# Sheet_1.net
KiCad netlist of a schematic drawn in Altium Designer
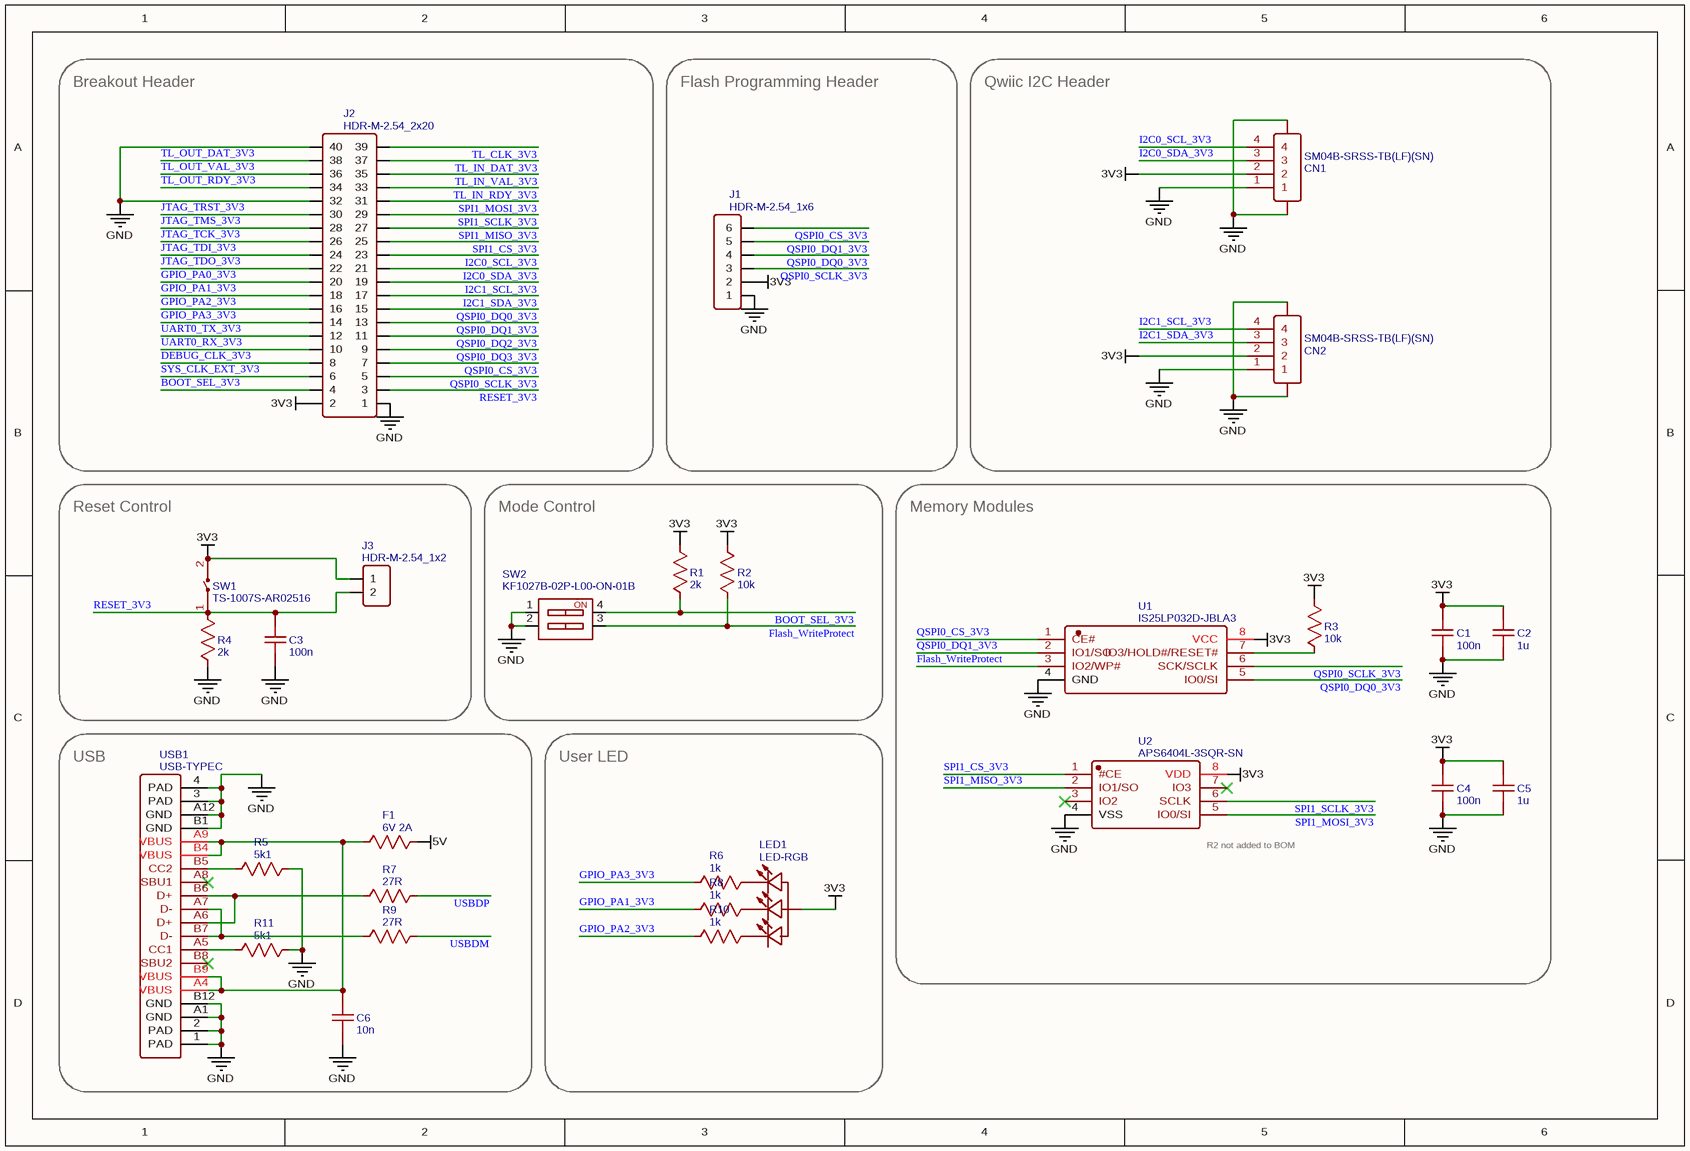
[diagram p0: Sheet_1.schdoc]

(export (version "E")
  (design (tool "Eeschema 10.0.6"))
  (components
    (comp (ref "C1")
      (value "100n")
      (footprint "CAPA-0402")
      (fields
        (field (name "BOM_SUPPLIER PART") "C307331")
        (field (name "BOM_MANUFACTURER PART") "CL05B104KB54PNC")
      )
      (libsource (lib "altium-import") (part "root_1_100n_"))
    )
    (comp (ref "C2")
      (value "1u")
      (footprint "CAPA-0402")
      (fields
        (field (name "BOM_SUPPLIER PART") "C52923")
        (field (name "BOM_MANUFACTURER PART") "CL05A105KA5NQNC")
      )
      (libsource (lib "altium-import") (part "root_1_1u_"))
    )
    (comp (ref "C3")
      (value "100n")
      (footprint "CAPA-0402")
      (fields
        (field (name "BOM_SUPPLIER PART") "C307331")
        (field (name "BOM_MANUFACTURER PART") "CL05B104KB54PNC")
      )
      (libsource (lib "altium-import") (part "root_1_100n_"))
    )
    (comp (ref "C4")
      (value "100n")
      (footprint "CAPA-0402")
      (fields
        (field (name "BOM_SUPPLIER PART") "C307331")
        (field (name "BOM_MANUFACTURER PART") "CL05B104KB54PNC")
      )
      (libsource (lib "altium-import") (part "root_1_100n_"))
    )
    (comp (ref "C5")
      (value "1u")
      (footprint "CAPA-0402")
      (fields
        (field (name "BOM_SUPPLIER PART") "C52923")
        (field (name "BOM_MANUFACTURER PART") "CL05A105KA5NQNC")
      )
      (libsource (lib "altium-import") (part "root_1_1u_"))
    )
    (comp (ref "C6")
      (value "10n")
      (footprint "CAPA-0402")
      (fields
        (field (name "BOM_SUPPLIER PART") "C15195")
        (field (name "BOM_MANUFACTURER PART") "CL05B103KB5NNNC")
      )
      (libsource (lib "altium-import") (part "root_1_10n_"))
    )
    (comp (ref "CN1")
      (value "SM04B-SRSS-TB(LF)(SN)")
      (footprint "CONN-SMD_4P-P1.00_SM04B-SRSS-TB-LF-SN")
      (fields (field (name "BOM_SUPPLIER PART") "C160404"))
      (libsource (lib "altium-import") (part "root_0_SM04B-SRSS-TB(LF)(SN)_"))
    )
    (comp (ref "CN2")
      (value "SM04B-SRSS-TB(LF)(SN)")
      (footprint "CONN-SMD_4P-P1.00_SM04B-SRSS-TB-LF-SN")
      (fields (field (name "BOM_SUPPLIER PART") "C160404"))
      (libsource (lib "altium-import") (part "root_0_SM04B-SRSS-TB(LF)(SN)_"))
    )
    (comp (ref "F1")
      (value "6V 2A")
      (footprint "R0805")
      (fields
        (field (name "BOM_SUPPLIER PART") "C70158")
        (field (name "BOM_MANUFACTURER PART") "SL0805200")
        (field (name "CONTRIBUTOR") "LCEDA_Lib")
      )
      (libsource (lib "altium-import") (part "root_0_6V 2A_"))
    )
    (comp (ref "J1")
      (value "HDR-M-2.54_1x6")
      (footprint "HDR-M-2.54_1X6")
      (fields (field (name "BOM_SUPPLIER PART") "C190819") (field (name "CONTRIBUTOR") "LCEDA_Lib"))
      (libsource (lib "altium-import") (part "root_2_HDR-M-2.54_1x6_"))
    )
    (comp (ref "J2")
      (value "HDR-M-2.54_2x20")
      (footprint "HDR-M-2.54_2X20")
      (fields (field (name "BOM_SUPPLIER PART") "C50980") (field (name "CONTRIBUTOR") "LCEDA_Lib"))
      (libsource (lib "altium-import") (part "root_2_HDR-M-2.54_2x20_"))
    )
    (comp (ref "J3")
      (value "HDR-M-2.54_1x2")
      (footprint "HDR-M-2.54_1X2")
      (fields (field (name "BOM_SUPPLIER PART") "C124375") (field (name "CONTRIBUTOR") "LCEDA_Lib"))
      (libsource (lib "altium-import") (part "root_0_HDR-M-2.54_1x2_"))
    )
    (comp (ref "LED1")
      (value "LED-RGB")
      (footprint "LED-ARRAY-SMD_4P-L3.2-W2.7-TL-RD_TJ-S3528")
      (fields
        (field (name "BOM_SUPPLIER PART") "C601699")
        (field (name "BOM_MANUFACTURER PART") "TJ-S3528UG2W9TLCCYRGB-A5")
      )
      (libsource (lib "altium-import") (part "root_0_LED-RGB_"))
    )
    (comp (ref "R1")
      (value "2k")
      (footprint "RES-0402")
      (fields
        (field (name "BOM_SUPPLIER PART") "C4109")
        (field (name "BOM_MANUFACTURER PART") "0402WGF2001TCE")
      )
      (libsource (lib "altium-import") (part "root_1_2k_"))
    )
    (comp (ref "R2")
      (value "10k")
      (footprint "RES-0402")
      (fields
        (field (name "BOM_SUPPLIER PART") "C25744")
        (field (name "BOM_MANUFACTURER PART") "0402WGF1002TCE")
      )
      (libsource (lib "altium-import") (part "root_1_10k_"))
    )
    (comp (ref "R3")
      (value "10k")
      (footprint "RES-0402")
      (fields
        (field (name "BOM_SUPPLIER PART") "C25744")
        (field (name "BOM_MANUFACTURER PART") "0402WGF1002TCE")
      )
      (libsource (lib "altium-import") (part "root_1_10k_"))
    )
    (comp (ref "R4")
      (value "2k")
      (footprint "RES-0402")
      (fields
        (field (name "BOM_SUPPLIER PART") "C4109")
        (field (name "BOM_MANUFACTURER PART") "0402WGF2001TCE")
      )
      (libsource (lib "altium-import") (part "root_1_2k_"))
    )
    (comp (ref "R5")
      (value "5k1")
      (footprint "RES-0402")
      (fields
        (field (name "BOM_SUPPLIER PART") "C25905")
        (field (name "BOM_MANUFACTURER PART") "0402WGF5101TCE")
      )
      (libsource (lib "altium-import") (part "root_0_5k1_"))
    )
    (comp (ref "R6")
      (value "1k")
      (footprint "RES-0402")
      (fields
        (field (name "BOM_SUPPLIER PART") "C11702")
        (field (name "BOM_MANUFACTURER PART") "0402WGF1001TCE")
      )
      (libsource (lib "altium-import") (part "root_2_1k_"))
    )
    (comp (ref "R7")
      (value "27R")
      (footprint "RES-0402")
      (fields
        (field (name "BOM_SUPPLIER PART") "C174257")
        (field (name "BOM_MANUFACTURER PART") "RCT0227RJLF")
      )
      (libsource (lib "altium-import") (part "root_0_27R_"))
    )
    (comp (ref "R8")
      (value "1k")
      (footprint "RES-0402")
      (fields
        (field (name "BOM_SUPPLIER PART") "C11702")
        (field (name "BOM_MANUFACTURER PART") "0402WGF1001TCE")
      )
      (libsource (lib "altium-import") (part "root_2_1k_"))
    )
    (comp (ref "R9")
      (value "27R")
      (footprint "RES-0402")
      (fields
        (field (name "BOM_SUPPLIER PART") "C174257")
        (field (name "BOM_MANUFACTURER PART") "RCT0227RJLF")
      )
      (libsource (lib "altium-import") (part "root_0_27R_"))
    )
    (comp (ref "R10")
      (value "1k")
      (footprint "RES-0402")
      (fields
        (field (name "BOM_SUPPLIER PART") "C11702")
        (field (name "BOM_MANUFACTURER PART") "0402WGF1001TCE")
      )
      (libsource (lib "altium-import") (part "root_2_1k_"))
    )
    (comp (ref "R11")
      (value "5k1")
      (footprint "RES-0402")
      (fields
        (field (name "BOM_SUPPLIER PART") "C25905")
        (field (name "BOM_MANUFACTURER PART") "0402WGF5101TCE")
      )
      (libsource (lib "altium-import") (part "root_0_5k1_"))
    )
    (comp (ref "SW1")
      (value "TS-1007S-AR02516")
      (footprint "SW-SMD_L6.1-W3.6-LS7.9")
      (fields (field (name "BOM_SUPPLIER PART") "C720381") (field (name "CONTRIBUTOR") "LCSC"))
      (libsource (lib "altium-import") (part "root_1_TS-1007S-AR02516_"))
    )
    (comp (ref "SW2")
      (value "KF1027B-02P-L00-ON-01B")
      (footprint "SW-SMD_4P-L6.1-W6.2-P2.54-LS10.0")
      (fields (field (name "BOM_SUPPLIER PART") "C976353") (field (name "CONTRIBUTOR") "LCSC"))
      (libsource (lib "altium-import") (part "root_3_KF1027B-02P-L00-ON-01B_"))
    )
    (comp (ref "U1")
      (value "IS25LP032D-JBLA3")
      (footprint "SOIC-8_L5.3-W5.3-P1.27-LS7.9-BL")
      (fields (field (name "BOM_SUPPLIER PART") "C1236833"))
      (libsource (lib "altium-import") (part "root_0_IS25LP032D-JBLA3_"))
    )
    (comp (ref "U2")
      (value "APS6404L-3SQR-SN")
      (footprint "SOIC-8_L5.0-W4.0-P1.27-LS6.0-TL")
      (fields (field (name "BOM_SUPPLIER PART") "C9900003354"))
      (libsource (lib "altium-import") (part "root_0_APS6404L-3SQR-SN_"))
    )
    (comp (ref "USB1")
      (value "USB-TYPEC")
      (footprint "USB-C-SMD_KH-TYPE-C-16P")
      (fields
        (field (name "BOM_MANUFACTURER PART") "KH-TYPE-C-16P")
        (field (name "BOM_SUPPLIER PART") "C709357")
        (field (name "CONTRIBUTOR") "T-K-233")
      )
      (libsource (lib "altium-import") (part "root_2_USB-TYPEC_"))
    )
  )
  (nets
    (net (code "1") (name "/BOOT_SEL_3V3") (class "Default")
      (node (ref "J2") (pin "4") (pinfunction "4_4") (pintype "passive"))
      (node (ref "R1") (pin "1") (pinfunction "1_1") (pintype "passive"))
      (node (ref "SW2") (pin "4") (pinfunction "A4_4") (pintype "passive"))
    )
    (net (code "2") (name "/DEBUG_CLK_3V3") (class "Default")
      (node (ref "J2") (pin "8") (pinfunction "8_8") (pintype "passive"))
    )
    (net (code "3") (name "/Flash_WriteProtect") (class "Default")
      (node (ref "R2") (pin "1") (pinfunction "1_1") (pintype "passive"))
      (node (ref "SW2") (pin "3") (pinfunction "A3_3") (pintype "passive"))
      (node (ref "U1") (pin "3") (pinfunction "IO2/WP#_3") (pintype "passive"))
    )
    (net (code "4") (name "/GPIO_PA0_3V3") (class "Default")
      (node (ref "J2") (pin "20") (pinfunction "20_20") (pintype "passive"))
    )
    (net (code "5") (name "/GPIO_PA1_3V3") (class "Default")
      (node (ref "J2") (pin "18") (pinfunction "18_18") (pintype "passive"))
      (node (ref "R8") (pin "2") (pinfunction "2_2") (pintype "passive"))
    )
    (net (code "6") (name "/GPIO_PA2_3V3") (class "Default")
      (node (ref "J2") (pin "16") (pinfunction "16_16") (pintype "passive"))
      (node (ref "R10") (pin "2") (pinfunction "2_2") (pintype "passive"))
    )
    (net (code "7") (name "/GPIO_PA3_3V3") (class "Default")
      (node (ref "J2") (pin "14") (pinfunction "14_14") (pintype "passive"))
      (node (ref "R6") (pin "2") (pinfunction "2_2") (pintype "passive"))
    )
    (net (code "8") (name "/I2C0_SCL_3V3") (class "Default")
      (node (ref "CN1") (pin "4") (pinfunction "4_4") (pintype "passive"))
      (node (ref "J2") (pin "23") (pinfunction "23_23") (pintype "passive"))
    )
    (net (code "9") (name "/I2C0_SDA_3V3") (class "Default")
      (node (ref "CN1") (pin "3") (pinfunction "3_3") (pintype "passive"))
      (node (ref "J2") (pin "21") (pinfunction "21_21") (pintype "passive"))
    )
    (net (code "10") (name "/I2C1_SCL_3V3") (class "Default")
      (node (ref "CN2") (pin "4") (pinfunction "4_4") (pintype "passive"))
      (node (ref "J2") (pin "19") (pinfunction "19_19") (pintype "passive"))
    )
    (net (code "11") (name "/I2C1_SDA_3V3") (class "Default")
      (node (ref "CN2") (pin "3") (pinfunction "3_3") (pintype "passive"))
      (node (ref "J2") (pin "17") (pinfunction "17_17") (pintype "passive"))
    )
    (net (code "12") (name "/JTAG_TCK_3V3") (class "Default")
      (node (ref "J2") (pin "26") (pinfunction "26_26") (pintype "passive"))
    )
    (net (code "13") (name "/JTAG_TDI_3V3") (class "Default")
      (node (ref "J2") (pin "24") (pinfunction "24_24") (pintype "passive"))
    )
    (net (code "14") (name "/JTAG_TDO_3V3") (class "Default")
      (node (ref "J2") (pin "22") (pinfunction "22_22") (pintype "passive"))
    )
    (net (code "15") (name "/JTAG_TMS_3V3") (class "Default")
      (node (ref "J2") (pin "28") (pinfunction "28_28") (pintype "passive"))
    )
    (net (code "16") (name "/JTAG_TRST_3V3") (class "Default")
      (node (ref "J2") (pin "30") (pinfunction "30_30") (pintype "passive"))
    )
    (net (code "17") (name "/QSPI0_CS_3V3") (class "Default")
      (node (ref "J1") (pin "6") (pinfunction "6_6") (pintype "passive"))
      (node (ref "J2") (pin "7") (pinfunction "7_7") (pintype "passive"))
      (node (ref "U1") (pin "1") (pinfunction "CE#_1") (pintype "passive"))
    )
    (net (code "18") (name "/QSPI0_DQ0_3V3") (class "Default")
      (node (ref "J1") (pin "4") (pinfunction "4_4") (pintype "passive"))
      (node (ref "J2") (pin "15") (pinfunction "15_15") (pintype "passive"))
      (node (ref "U1") (pin "5") (pinfunction "IO0/SI_5") (pintype "passive"))
    )
    (net (code "19") (name "/QSPI0_DQ1_3V3") (class "Default")
      (node (ref "J1") (pin "5") (pinfunction "5_5") (pintype "passive"))
      (node (ref "J2") (pin "13") (pinfunction "13_13") (pintype "passive"))
      (node (ref "U1") (pin "2") (pinfunction "IO1/SO_2") (pintype "passive"))
    )
    (net (code "20") (name "/QSPI0_DQ2_3V3") (class "Default")
      (node (ref "J2") (pin "11") (pinfunction "11_11") (pintype "passive"))
    )
    (net (code "21") (name "/QSPI0_DQ3_3V3") (class "Default")
      (node (ref "J2") (pin "9") (pinfunction "9_9") (pintype "passive"))
    )
    (net (code "22") (name "/QSPI0_SCLK_3V3") (class "Default")
      (node (ref "J1") (pin "3") (pinfunction "3_3") (pintype "passive"))
      (node (ref "J2") (pin "5") (pinfunction "5_5") (pintype "passive"))
      (node (ref "U1") (pin "6") (pinfunction "SCK/SCLK_6") (pintype "passive"))
    )
    (net (code "23") (name "/RESET_3V3") (class "Default")
      (node (ref "C3") (pin "2") (pinfunction "2_2") (pintype "passive"))
      (node (ref "J2") (pin "3") (pinfunction "3_3") (pintype "passive"))
      (node (ref "J3") (pin "2") (pinfunction "2_2") (pintype "passive"))
      (node (ref "R4") (pin "2") (pinfunction "2_2") (pintype "passive"))
      (node (ref "SW1") (pin "1") (pinfunction "1_1") (pintype "passive"))
    )
    (net (code "24") (name "/SPI1_CS_3V3") (class "Default")
      (node (ref "J2") (pin "25") (pinfunction "25_25") (pintype "passive"))
      (node (ref "U2") (pin "1") (pinfunction "#CE_1") (pintype "passive"))
    )
    (net (code "25") (name "/SPI1_MISO_3V3") (class "Default")
      (node (ref "J2") (pin "27") (pinfunction "27_27") (pintype "passive"))
      (node (ref "U2") (pin "2") (pinfunction "IO1/SO_2") (pintype "passive"))
    )
    (net (code "26") (name "/SPI1_MOSI_3V3") (class "Default")
      (node (ref "J2") (pin "31") (pinfunction "31_31") (pintype "passive"))
      (node (ref "U2") (pin "5") (pinfunction "IO0/SI_5") (pintype "passive"))
    )
    (net (code "27") (name "/SPI1_SCLK_3V3") (class "Default")
      (node (ref "J2") (pin "29") (pinfunction "29_29") (pintype "passive"))
      (node (ref "U2") (pin "6") (pinfunction "SCLK_6") (pintype "passive"))
    )
    (net (code "28") (name "/SYS_CLK_EXT_3V3") (class "Default")
      (node (ref "J2") (pin "6") (pinfunction "6_6") (pintype "passive"))
    )
    (net (code "29") (name "/TL_CLK_3V3") (class "Default")
      (node (ref "J2") (pin "39") (pinfunction "39_39") (pintype "passive"))
    )
    (net (code "30") (name "/TL_IN_DAT_3V3") (class "Default")
      (node (ref "J2") (pin "37") (pinfunction "37_37") (pintype "passive"))
    )
    (net (code "31") (name "/TL_IN_RDY_3V3") (class "Default")
      (node (ref "J2") (pin "33") (pinfunction "33_33") (pintype "passive"))
    )
    (net (code "32") (name "/TL_IN_VAL_3V3") (class "Default")
      (node (ref "J2") (pin "35") (pinfunction "35_35") (pintype "passive"))
    )
    (net (code "33") (name "/TL_OUT_DAT_3V3") (class "Default")
      (node (ref "J2") (pin "38") (pinfunction "38_38") (pintype "passive"))
    )
    (net (code "34") (name "/TL_OUT_RDY_3V3") (class "Default")
      (node (ref "J2") (pin "34") (pinfunction "34_34") (pintype "passive"))
    )
    (net (code "35") (name "/TL_OUT_VAL_3V3") (class "Default")
      (node (ref "J2") (pin "36") (pinfunction "36_36") (pintype "passive"))
    )
    (net (code "36") (name "/UART0_RX_3V3") (class "Default")
      (node (ref "J2") (pin "10") (pinfunction "10_10") (pintype "passive"))
    )
    (net (code "37") (name "/UART0_TX_3V3") (class "Default")
      (node (ref "J2") (pin "12") (pinfunction "12_12") (pintype "passive"))
    )
    (net (code "38") (name "/USBDM") (class "Default")
      (node (ref "R9") (pin "2") (pinfunction "2_2") (pintype "passive"))
    )
    (net (code "39") (name "/USBDP") (class "Default")
      (node (ref "R7") (pin "2") (pinfunction "2_2") (pintype "passive"))
    )
    (net (code "40") (name "3V3") (class "Default")
      (node (ref "C1") (pin "2") (pinfunction "2_2") (pintype "passive"))
      (node (ref "C2") (pin "2") (pinfunction "2_2") (pintype "passive"))
      (node (ref "C4") (pin "2") (pinfunction "2_2") (pintype "passive"))
      (node (ref "C5") (pin "2") (pinfunction "2_2") (pintype "passive"))
      (node (ref "CN1") (pin "2") (pinfunction "2_2") (pintype "passive"))
      (node (ref "CN2") (pin "2") (pinfunction "2_2") (pintype "passive"))
      (node (ref "J1") (pin "2") (pinfunction "2_2") (pintype "passive"))
      (node (ref "J2") (pin "2") (pinfunction "2_2") (pintype "passive"))
      (node (ref "J3") (pin "1") (pinfunction "1_1") (pintype "passive"))
      (node (ref "LED1") (pin "4") (pinfunction "+_4") (pintype "passive"))
      (node (ref "R1") (pin "2") (pinfunction "2_2") (pintype "passive"))
      (node (ref "R2") (pin "2") (pinfunction "2_2") (pintype "passive"))
      (node (ref "R3") (pin "2") (pinfunction "2_2") (pintype "passive"))
      (node (ref "SW1") (pin "2") (pinfunction "2_2") (pintype "passive"))
      (node (ref "U1") (pin "8") (pinfunction "VCC_8") (pintype "passive"))
      (node (ref "U2") (pin "8") (pinfunction "VDD_8") (pintype "passive"))
    )
    (net (code "41") (name "5V") (class "Default")
      (node (ref "F1") (pin "2") (pinfunction "2_2") (pintype "passive"))
    )
    (net (code "42") (name "GND") (class "Default")
      (node (ref "C1") (pin "1") (pinfunction "1_1") (pintype "passive"))
      (node (ref "C2") (pin "1") (pinfunction "1_1") (pintype "passive"))
      (node (ref "C3") (pin "1") (pinfunction "1_1") (pintype "passive"))
      (node (ref "C4") (pin "1") (pinfunction "1_1") (pintype "passive"))
      (node (ref "C5") (pin "1") (pinfunction "1_1") (pintype "passive"))
      (node (ref "C6") (pin "1") (pinfunction "1_1") (pintype "passive"))
      (node (ref "CN1") (pin "1") (pinfunction "1_1") (pintype "passive"))
      (node (ref "CN1") (pin "5") (pinfunction "5_5") (pintype "passive"))
      (node (ref "CN1") (pin "6") (pinfunction "6_6") (pintype "passive"))
      (node (ref "CN2") (pin "1") (pinfunction "1_1") (pintype "passive"))
      (node (ref "CN2") (pin "5") (pinfunction "5_5") (pintype "passive"))
      (node (ref "CN2") (pin "6") (pinfunction "6_6") (pintype "passive"))
      (node (ref "J1") (pin "1") (pinfunction "1_1") (pintype "passive"))
      (node (ref "J2") (pin "1") (pinfunction "1_1") (pintype "passive"))
      (node (ref "J2") (pin "32") (pinfunction "32_32") (pintype "passive"))
      (node (ref "J2") (pin "40") (pinfunction "40_40") (pintype "passive"))
      (node (ref "R11") (pin "2") (pinfunction "2_2") (pintype "passive"))
      (node (ref "R4") (pin "1") (pinfunction "1_1") (pintype "passive"))
      (node (ref "R5") (pin "2") (pinfunction "2_2") (pintype "passive"))
      (node (ref "SW2") (pin "1") (pinfunction "A1_1") (pintype "passive"))
      (node (ref "SW2") (pin "2") (pinfunction "A2_2") (pintype "passive"))
      (node (ref "U1") (pin "4") (pinfunction "GND_4") (pintype "passive"))
      (node (ref "U2") (pin "4") (pinfunction "VSS_4") (pintype "passive"))
      (node (ref "USB1") (pin "1") (pinfunction "PAD_1") (pintype "passive"))
      (node (ref "USB1") (pin "2") (pinfunction "PAD_2") (pintype "passive"))
      (node (ref "USB1") (pin "3") (pinfunction "PAD_3") (pintype "passive"))
      (node (ref "USB1") (pin "4") (pinfunction "PAD_4") (pintype "passive"))
      (node (ref "USB1") (pin "A1") (pinfunction "GND_A1") (pintype "passive"))
      (node (ref "USB1") (pin "A12") (pinfunction "GND_A12") (pintype "passive"))
      (node (ref "USB1") (pin "B1") (pinfunction "GND_B1") (pintype "passive"))
      (node (ref "USB1") (pin "B12") (pinfunction "GND_B12") (pintype "passive"))
    )
    (net (code "43") (name "Net-(C6-Pad2)") (class "Default")
      (node (ref "C6") (pin "2") (pinfunction "2_2") (pintype "passive"))
      (node (ref "F1") (pin "1") (pinfunction "1_1") (pintype "passive"))
      (node (ref "USB1") (pin "A4") (pinfunction "VBUS_A4") (pintype "passive"))
      (node (ref "USB1") (pin "A9") (pinfunction "VBUS_A9") (pintype "passive"))
      (node (ref "USB1") (pin "B4") (pinfunction "VBUS_B4") (pintype "passive"))
      (node (ref "USB1") (pin "B9") (pinfunction "VBUS_B9") (pintype "passive"))
    )
    (net (code "44") (name "Net-(LED1---Pad1)") (class "Default")
      (node (ref "LED1") (pin "1") (pinfunction "-_1") (pintype "passive"))
      (node (ref "R8") (pin "1") (pinfunction "1_1") (pintype "passive"))
    )
    (net (code "45") (name "Net-(LED1---Pad2)") (class "Default")
      (node (ref "LED1") (pin "2") (pinfunction "-_2") (pintype "passive"))
      (node (ref "R10") (pin "1") (pinfunction "1_1") (pintype "passive"))
    )
    (net (code "46") (name "Net-(LED1---Pad3)") (class "Default")
      (node (ref "LED1") (pin "3") (pinfunction "-_3") (pintype "passive"))
      (node (ref "R6") (pin "1") (pinfunction "1_1") (pintype "passive"))
    )
    (net (code "47") (name "Net-(R7-Pad1)") (class "Default")
      (node (ref "R7") (pin "1") (pinfunction "1_1") (pintype "passive"))
      (node (ref "USB1") (pin "A6") (pinfunction "D+_A6") (pintype "passive"))
      (node (ref "USB1") (pin "B6") (pinfunction "D+_B6") (pintype "passive"))
    )
    (net (code "48") (name "Net-(R9-Pad1)") (class "Default")
      (node (ref "R9") (pin "1") (pinfunction "1_1") (pintype "passive"))
      (node (ref "USB1") (pin "A7") (pinfunction "D-_A7") (pintype "passive"))
      (node (ref "USB1") (pin "B7") (pinfunction "D-_B7") (pintype "passive"))
    )
    (net (code "49") (name "Net-(U1-IO3{slash}HOLD#{slash}RESET#)") (class "Default")
      (node (ref "R3") (pin "1") (pinfunction "1_1") (pintype "passive"))
      (node (ref "U1") (pin "7") (pinfunction "IO3/HOLD#/RESET#_7") (pintype "passive"))
    )
    (net (code "50") (name "Net-(USB1-CC1)") (class "Default")
      (node (ref "R11") (pin "1") (pinfunction "1_1") (pintype "passive"))
      (node (ref "USB1") (pin "A5") (pinfunction "CC1_A5") (pintype "passive"))
    )
    (net (code "51") (name "Net-(USB1-CC2)") (class "Default")
      (node (ref "R5") (pin "1") (pinfunction "1_1") (pintype "passive"))
      (node (ref "USB1") (pin "B5") (pinfunction "CC2_B5") (pintype "passive"))
    )
    (net (code "52") (name "unconnected-(U2-IO2-Pad3)") (class "Default")
      (node (ref "U2") (pin "3") (pinfunction "IO2_3") (pintype "passive+no_connect"))
    )
    (net (code "53") (name "unconnected-(U2-IO3-Pad7)") (class "Default")
      (node (ref "U2") (pin "7") (pinfunction "IO3_7") (pintype "passive+no_connect"))
    )
    (net (code "54") (name "unconnected-(USB1-SBU1-PadA8)") (class "Default")
      (node (ref "USB1") (pin "A8") (pinfunction "SBU1_A8") (pintype "passive+no_connect"))
    )
    (net (code "55") (name "unconnected-(USB1-SBU2-PadB8)") (class "Default")
      (node (ref "USB1") (pin "B8") (pinfunction "SBU2_B8") (pintype "passive+no_connect"))
    )
  )
)
